# SLink_Unit.net
KiCad netlist of a schematic drawn in Altium Designer
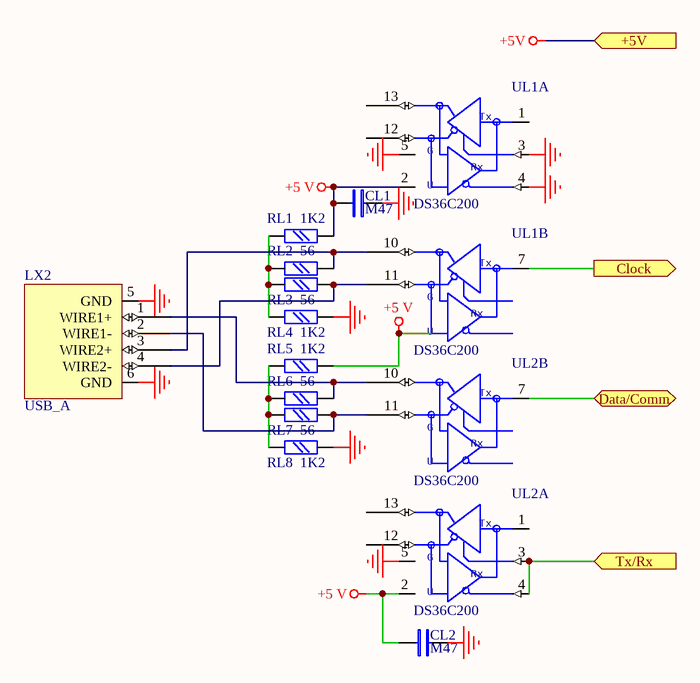
[diagram p0: SLink Unit.SchDoc]

(export (version "E")
  (design (tool "Eeschema 10.0.6"))
  (components
    (comp (ref "CL1") (value "M47") (footprint "chip0805") (libsource (lib "*") (part "C")))
    (comp (ref "CL2") (value "M47") (footprint "chip0805") (libsource (lib "*") (part "C")))
    (comp (ref "LX2") (value "USB_A") (footprint "USB-A") (libsource (lib "*") (part "USB_A")))
    (comp (ref "RL1") (value "1K2") (footprint "chip0805") (libsource (lib "*") (part "R")))
    (comp (ref "RL2") (value "56") (footprint "chip0805") (libsource (lib "*") (part "R")))
    (comp (ref "RL3") (value "56") (footprint "chip0805") (libsource (lib "*") (part "R")))
    (comp (ref "RL4") (value "1K2") (footprint "chip0805") (libsource (lib "*") (part "R")))
    (comp (ref "RL5") (value "1K2") (footprint "chip0805") (libsource (lib "*") (part "R")))
    (comp (ref "RL6") (value "56") (footprint "chip0805") (libsource (lib "*") (part "R")))
    (comp (ref "RL7") (value "56") (footprint "chip0805") (libsource (lib "*") (part "R")))
    (comp (ref "RL8") (value "1K2") (footprint "chip0805") (libsource (lib "*") (part "R")))
    (comp (ref "UL1") (value "DS36C200") (footprint "14SO200") (libsource (lib "*") (part "DS36C200")))
    (comp (ref "UL2") (value "DS36C200") (footprint "14SO200") (libsource (lib "*") (part "DS36C200")))
  )
  (nets
    (net (code "1") (name "+5 V") (class "Default")
      (node (ref "CL1") (pin "1") (pinfunction "1_1") (pintype "passive"))
      (node (ref "CL2") (pin "1") (pinfunction "1_1") (pintype "passive"))
      (node (ref "RL1") (pin "2") (pinfunction "2_2") (pintype "passive"))
      (node (ref "RL5") (pin "2") (pinfunction "2_2") (pintype "passive"))
      (node (ref "UL1") (pin "2") (pinfunction "VCC_2") (pintype "passive"))
      (node (ref "UL2") (pin "2") (pinfunction "VCC_2") (pintype "passive"))
    )
    (net (code "3") (name "/Clock") (class "Default")
      (node (ref "UL1") (pin "7") (pinfunction "DATA_7") (pintype "bidirectional"))
    )
    (net (code "4") (name "/Data{slash}Comm") (class "Default")
      (node (ref "UL2") (pin "7") (pinfunction "DATA_7") (pintype "bidirectional"))
    )
    (net (code "5") (name "/Tx{slash}Rx") (class "Default")
      (node (ref "UL2") (pin "3") (pinfunction "TE_3") (pintype "input"))
      (node (ref "UL2") (pin "4") (pinfunction "RE_4") (pintype "input"))
    )
    (net (code "6") (name "GND") (class "Default")
      (node (ref "CL1") (pin "2") (pinfunction "2_2") (pintype "passive"))
      (node (ref "CL2") (pin "2") (pinfunction "2_2") (pintype "passive"))
      (node (ref "LX2") (pin "5") (pinfunction "GND_5") (pintype "passive"))
      (node (ref "LX2") (pin "6") (pinfunction "GND_6") (pintype "passive"))
      (node (ref "RL4") (pin "2") (pinfunction "2_2") (pintype "passive"))
      (node (ref "RL8") (pin "2") (pinfunction "2_2") (pintype "passive"))
      (node (ref "UL1") (pin "3") (pinfunction "TE_3") (pintype "input"))
      (node (ref "UL1") (pin "4") (pinfunction "RE_4") (pintype "input"))
      (node (ref "UL1") (pin "5") (pinfunction "GND_5") (pintype "passive"))
      (node (ref "UL2") (pin "5") (pinfunction "GND_5") (pintype "passive"))
    )
    (net (code "7") (name "Net-(LX2-WIRE1+)") (class "Default")
      (node (ref "LX2") (pin "1") (pinfunction "WIRE1+_1") (pintype "bidirectional"))
      (node (ref "RL6") (pin "2") (pinfunction "2_2") (pintype "passive"))
      (node (ref "UL2") (pin "10") (pinfunction "WIRE+_10") (pintype "bidirectional"))
    )
    (net (code "8") (name "Net-(LX2-WIRE1-)") (class "Default")
      (node (ref "LX2") (pin "2") (pinfunction "WIRE1-_2") (pintype "bidirectional"))
      (node (ref "RL7") (pin "2") (pinfunction "2_2") (pintype "passive"))
      (node (ref "UL2") (pin "11") (pinfunction "WIRE-_11") (pintype "bidirectional"))
    )
    (net (code "9") (name "Net-(LX2-WIRE2+)") (class "Default")
      (node (ref "LX2") (pin "3") (pinfunction "WIRE2+_3") (pintype "bidirectional"))
      (node (ref "RL2") (pin "2") (pinfunction "2_2") (pintype "passive"))
      (node (ref "UL1") (pin "10") (pinfunction "WIRE+_10") (pintype "bidirectional"))
    )
    (net (code "10") (name "Net-(LX2-WIRE2-)") (class "Default")
      (node (ref "LX2") (pin "4") (pinfunction "WIRE2-_4") (pintype "bidirectional"))
      (node (ref "RL3") (pin "2") (pinfunction "2_2") (pintype "passive"))
      (node (ref "UL1") (pin "11") (pinfunction "WIRE-_11") (pintype "bidirectional"))
    )
    (net (code "11") (name "Net-(RL1-Pad1)") (class "Default")
      (node (ref "RL1") (pin "1") (pinfunction "1_1") (pintype "passive"))
      (node (ref "RL2") (pin "1") (pinfunction "1_1") (pintype "passive"))
      (node (ref "RL3") (pin "1") (pinfunction "1_1") (pintype "passive"))
      (node (ref "RL4") (pin "1") (pinfunction "1_1") (pintype "passive"))
    )
    (net (code "12") (name "Net-(RL5-Pad1)") (class "Default")
      (node (ref "RL5") (pin "1") (pinfunction "1_1") (pintype "passive"))
      (node (ref "RL6") (pin "1") (pinfunction "1_1") (pintype "passive"))
      (node (ref "RL7") (pin "1") (pinfunction "1_1") (pintype "passive"))
      (node (ref "RL8") (pin "1") (pinfunction "1_1") (pintype "passive"))
    )
    (net (code "13") (name "unconnected-(UL1A-DATA-Pad1)") (class "Default")
      (node (ref "UL1") (pin "1") (pinfunction "DATA_1") (pintype "bidirectional"))
    )
    (net (code "14") (name "unconnected-(UL1A-WIRE+-Pad13)") (class "Default")
      (node (ref "UL1") (pin "13") (pinfunction "WIRE+_13") (pintype "bidirectional"))
    )
    (net (code "15") (name "unconnected-(UL1A-WIRE--Pad12)") (class "Default")
      (node (ref "UL1") (pin "12") (pinfunction "WIRE-_12") (pintype "bidirectional"))
    )
    (net (code "16") (name "unconnected-(UL2A-DATA-Pad1)") (class "Default")
      (node (ref "UL2") (pin "1") (pinfunction "DATA_1") (pintype "bidirectional"))
    )
    (net (code "17") (name "unconnected-(UL2A-WIRE+-Pad13)") (class "Default")
      (node (ref "UL2") (pin "13") (pinfunction "WIRE+_13") (pintype "bidirectional"))
    )
    (net (code "18") (name "unconnected-(UL2A-WIRE--Pad12)") (class "Default")
      (node (ref "UL2") (pin "12") (pinfunction "WIRE-_12") (pintype "bidirectional"))
    )
  )
)
